# RemoteMain.net
KiCad netlist of a schematic drawn in Altium Designer
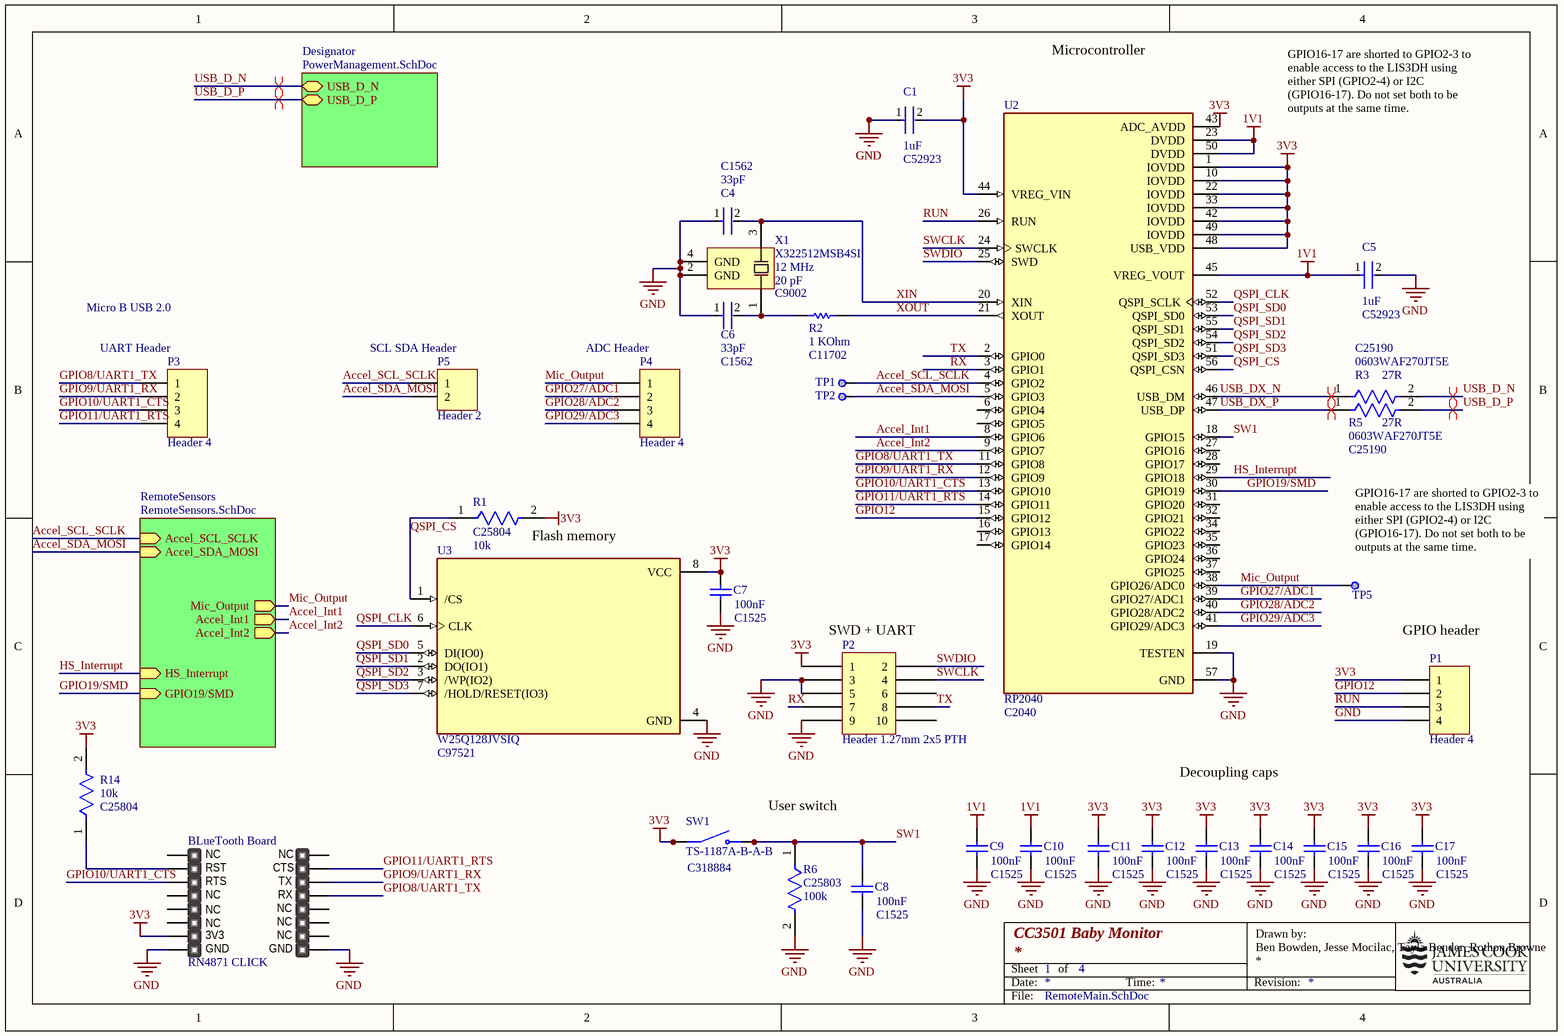
[diagram p0: RemoteMain.SchDoc]

(export (version "E")
  (design (tool "Eeschema 10.0.6"))
  (components
    (comp (ref "BLueTooth Board")
      (value "RN4871 CLICK")
      (footprint "mikroBUS - Large")
      (description "mikroBUS compatible add-on board")
      (libsource (lib "James Cook University") (part "RN4871 Click"))
    )
    (comp (ref "C1")
      (value "CL05A105KA5NQNC")
      (footprint "FP-CL542-IPC_C")
      (description "Cap Ceramic 1uF 25V X5R ±10% SMD 0402 +85°C Paper T/R")
      (fields
        (field (name "JLCPCB PART") "C52923")
        (field (name "CAPACITANCE") "1uF")
        (field (name "TOLERANCE") "10%")
      )
      (libsource (lib "James Cook University") (part "b4654b650e69147ec39a6b967a45e02"))
    )
    (comp (ref "C4")
      (value "0402CG330J500NT")
      (footprint "FP-0402-L_1_0_1-W_0_5_0_1-IPC_A")
      (description "General Purpose Ceramic Capacitor, 0402, 33pF, 5%, C0G, 30ppm/°C, 50V")
      (fields
        (field (name "VOLTAGE") "50V")
        (field (name "JLCPCB PART") "C1562")
        (field (name "CAPACITANCE") "33pF")
        (field (name "TOLERANCE") "5%")
      )
      (libsource (lib "James Cook University") (part "b4654b650e69147ec39a6b967a45e02"))
    )
    (comp (ref "C5")
      (value "CL05A105KA5NQNC")
      (footprint "FP-CL542-IPC_C")
      (description "Cap Ceramic 1uF 25V X5R ±10% SMD 0402 +85°C Paper T/R")
      (fields
        (field (name "JLCPCB PART") "C52923")
        (field (name "CAPACITANCE") "1uF")
        (field (name "TOLERANCE") "10%")
      )
      (libsource (lib "James Cook University") (part "b4654b650e69147ec39a6b967a45e02"))
    )
    (comp (ref "C6")
      (value "0402CG330J500NT")
      (footprint "FP-0402-L_1_0_1-W_0_5_0_1-IPC_A")
      (description "General Purpose Ceramic Capacitor, 0402, 33pF, 5%, C0G, 30ppm/°C, 50V")
      (fields
        (field (name "VOLTAGE") "50V")
        (field (name "JLCPCB PART") "C1562")
        (field (name "CAPACITANCE") "33pF")
        (field (name "TOLERANCE") "5%")
      )
      (libsource (lib "James Cook University") (part "b4654b650e69147ec39a6b967a45e02"))
    )
    (comp (ref "C7")
      (value "CL05B104KO5NNNC")
      (footprint "CAPC1050X55X23ML05T13")
      (description "Chip Capacitor, 100 nF, +/- 10%, 16 V, -55 to 125 degC, 0402 (1005 Metric), RoHS, Tape and Reel")
      (fields
        (field (name "JLCPCB PART") "C1525")
        (field (name "CAPACITANCE") "100nF")
        (field (name "MANUFACTURER") "Samsung Electro-Mechanics")
      )
      (libsource (lib "James Cook University") (part "CAP-NP-2"))
    )
    (comp (ref "C8")
      (value "CL05B104KO5NNNC")
      (footprint "CAPC1050X55X23ML05T13")
      (description "Chip Capacitor, 100 nF, +/- 10%, 16 V, -55 to 125 degC, 0402 (1005 Metric), RoHS, Tape and Reel")
      (fields
        (field (name "JLCPCB PART") "C1525")
        (field (name "CAPACITANCE") "100nF")
        (field (name "MANUFACTURER") "Samsung Electro-Mechanics")
      )
      (libsource (lib "James Cook University") (part "CAP-NP-2"))
    )
    (comp (ref "C9")
      (value "CL05B104KO5NNNC")
      (footprint "CAPC1050X55X23ML05T13")
      (description "Chip Capacitor, 100 nF, +/- 10%, 16 V, -55 to 125 degC, 0402 (1005 Metric), RoHS, Tape and Reel")
      (fields
        (field (name "JLCPCB PART") "C1525")
        (field (name "CAPACITANCE") "100nF")
        (field (name "MANUFACTURER") "Samsung Electro-Mechanics")
      )
      (libsource (lib "James Cook University") (part "CAP-NP-2"))
    )
    (comp (ref "C10")
      (value "CL05B104KO5NNNC")
      (footprint "CAPC1050X55X23ML05T13")
      (description "Chip Capacitor, 100 nF, +/- 10%, 16 V, -55 to 125 degC, 0402 (1005 Metric), RoHS, Tape and Reel")
      (fields
        (field (name "JLCPCB PART") "C1525")
        (field (name "CAPACITANCE") "100nF")
        (field (name "MANUFACTURER") "Samsung Electro-Mechanics")
      )
      (libsource (lib "James Cook University") (part "CAP-NP-2"))
    )
    (comp (ref "C11")
      (value "CL05B104KO5NNNC")
      (footprint "CAPC1050X55X23ML05T13")
      (description "Chip Capacitor, 100 nF, +/- 10%, 16 V, -55 to 125 degC, 0402 (1005 Metric), RoHS, Tape and Reel")
      (fields
        (field (name "JLCPCB PART") "C1525")
        (field (name "CAPACITANCE") "100nF")
        (field (name "MANUFACTURER") "Samsung Electro-Mechanics")
      )
      (libsource (lib "James Cook University") (part "CAP-NP-2"))
    )
    (comp (ref "C12")
      (value "CL05B104KO5NNNC")
      (footprint "CAPC1050X55X23ML05T13")
      (description "Chip Capacitor, 100 nF, +/- 10%, 16 V, -55 to 125 degC, 0402 (1005 Metric), RoHS, Tape and Reel")
      (fields
        (field (name "JLCPCB PART") "C1525")
        (field (name "CAPACITANCE") "100nF")
        (field (name "MANUFACTURER") "Samsung Electro-Mechanics")
      )
      (libsource (lib "James Cook University") (part "CAP-NP-2"))
    )
    (comp (ref "C13")
      (value "CL05B104KO5NNNC")
      (footprint "CAPC1050X55X23ML05T13")
      (description "Chip Capacitor, 100 nF, +/- 10%, 16 V, -55 to 125 degC, 0402 (1005 Metric), RoHS, Tape and Reel")
      (fields
        (field (name "JLCPCB PART") "C1525")
        (field (name "CAPACITANCE") "100nF")
        (field (name "MANUFACTURER") "Samsung Electro-Mechanics")
      )
      (libsource (lib "James Cook University") (part "CAP-NP-2"))
    )
    (comp (ref "C14")
      (value "CL05B104KO5NNNC")
      (footprint "CAPC1050X55X23ML05T13")
      (description "Chip Capacitor, 100 nF, +/- 10%, 16 V, -55 to 125 degC, 0402 (1005 Metric), RoHS, Tape and Reel")
      (fields
        (field (name "JLCPCB PART") "C1525")
        (field (name "CAPACITANCE") "100nF")
        (field (name "MANUFACTURER") "Samsung Electro-Mechanics")
      )
      (libsource (lib "James Cook University") (part "CAP-NP-2"))
    )
    (comp (ref "C15")
      (value "CL05B104KO5NNNC")
      (footprint "CAPC1050X55X23ML05T13")
      (description "Chip Capacitor, 100 nF, +/- 10%, 16 V, -55 to 125 degC, 0402 (1005 Metric), RoHS, Tape and Reel")
      (fields
        (field (name "JLCPCB PART") "C1525")
        (field (name "CAPACITANCE") "100nF")
        (field (name "MANUFACTURER") "Samsung Electro-Mechanics")
      )
      (libsource (lib "James Cook University") (part "CAP-NP-2"))
    )
    (comp (ref "C16")
      (value "CL05B104KO5NNNC")
      (footprint "CAPC1050X55X23ML05T13")
      (description "Chip Capacitor, 100 nF, +/- 10%, 16 V, -55 to 125 degC, 0402 (1005 Metric), RoHS, Tape and Reel")
      (fields
        (field (name "JLCPCB PART") "C1525")
        (field (name "CAPACITANCE") "100nF")
        (field (name "MANUFACTURER") "Samsung Electro-Mechanics")
      )
      (libsource (lib "James Cook University") (part "CAP-NP-2"))
    )
    (comp (ref "C17")
      (value "CL05B104KO5NNNC")
      (footprint "CAPC1050X55X23ML05T13")
      (description "Chip Capacitor, 100 nF, +/- 10%, 16 V, -55 to 125 degC, 0402 (1005 Metric), RoHS, Tape and Reel")
      (fields
        (field (name "JLCPCB PART") "C1525")
        (field (name "CAPACITANCE") "100nF")
        (field (name "MANUFACTURER") "Samsung Electro-Mechanics")
      )
      (libsource (lib "James Cook University") (part "CAP-NP-2"))
    )
    (comp (ref "P1")
      (value "Header 4")
      (footprint "HDR1X4")
      (description "Header, 4-Pin")
      (fields (field (name "PUBLISHER") "Altium Limited"))
      (libsource (lib "James Cook University") (part "Header 4H"))
    )
    (comp (ref "P2")
      (value "Header 1.27mm 2x5 PTH")
      (footprint "Header 1.27mm 2x5 PTH")
      (description "Header 1.27mm pitch, 2x5, PTH through hole")
      (fields (field (name "SOURCE") "JCULibrary.SchLib"))
      (libsource (lib "James Cook University") (part "Header 1.27mm 2x5 PTH"))
    )
    (comp (ref "P3")
      (value "Header 4")
      (footprint "HDR1X4")
      (description "Header, 4-Pin")
      (fields (field (name "PUBLISHER") "Altium Limited"))
      (libsource (lib "James Cook University") (part "Header 4H"))
    )
    (comp (ref "P4")
      (value "Header 4")
      (footprint "HDR1X4")
      (description "Header, 4-Pin")
      (fields (field (name "PUBLISHER") "Altium Limited"))
      (libsource (lib "James Cook University") (part "Header 4H"))
    )
    (comp (ref "P5")
      (value "Header 2")
      (footprint "HDR1X2")
      (description "Header, 2-Pin")
      (fields (field (name "PUBLISHER") "Altium Limited"))
      (libsource (lib "James Cook University") (part "Header 2H"))
    )
    (comp (ref "R1")
      (value "0603WAF1002T5E")
      (footprint "FP-CRCW0603-e3-IPC_B")
      (description "RES Thick Film, 10kΩ, 1%, 0.1W, 100ppm/°C, 0603")
      (fields
        (field (name "TOLERANCE") "1%")
        (field (name "JLCPCB PART") "C25804")
        (field (name "RESISTANCE") "10k")
      )
      (libsource (lib "James Cook University") (part "1029c3af85768c4190bb7ad29bc67b5"))
    )
    (comp (ref "R2")
      (value "0402WGF1001TCE")
      (footprint "RESC1005X40X25NL05T05")
      (description "Chip Resistor, 1 KOhm, +/- 1%, 100 mW, -55 to 155 degC, 0402 (1005 Metric), RoHS, Tape and Reel")
      (fields
        (field (name "RESISTANCE") "1 KOhm")
        (field (name "JLCPCB PART") "C11702")
        (field (name "TOLERANCE") "1%")
        (field (name "MANUFACTURER") "Basic Passives")
      )
      (libsource (lib "James Cook University") (part "RES-2"))
    )
    (comp (ref "R3")
      (value "0603WAF270JT5E")
      (footprint "FP-CRCW0603-e3-IPC_B")
      (description "RES Thick Film, 27Ω, 1%, 0.1W, 200ppm/°C, 0603")
      (fields
        (field (name "JLCPCB PART") "C25190")
        (field (name "RESISTANCE") "27R")
        (field (name "TOLERANCE") "1%")
      )
      (libsource (lib "James Cook University") (part "1029c3af85768c4190bb7ad29bc67b5"))
    )
    (comp (ref "R5")
      (value "0603WAF270JT5E")
      (footprint "FP-CRCW0603-e3-IPC_B")
      (description "RES Thick Film, 27Ω, 1%, 0.1W, 200ppm/°C, 0603")
      (fields
        (field (name "JLCPCB PART") "C25190")
        (field (name "RESISTANCE") "27R")
        (field (name "TOLERANCE") "1%")
      )
      (libsource (lib "James Cook University") (part "1029c3af85768c4190bb7ad29bc67b5"))
    )
    (comp (ref "R6")
      (value "0603WAF1003T5E")
      (footprint "FP-CRCW0603-e3-IPC_B")
      (description "RES Thick Film, 100kΩ, 1%, 0.1W, 100ppm/°C, 0603")
      (fields
        (field (name "JLCPCB PART") "C25803")
        (field (name "RESISTANCE") "100k")
        (field (name "TOLERANCE") "1%")
      )
      (libsource (lib "James Cook University") (part "1029c3af85768c4190bb7ad29bc67b5"))
    )
    (comp (ref "R14")
      (value "0603WAF1002T5E")
      (footprint "FP-CRCW0603-e3-IPC_B")
      (description "RES Thick Film, 10kΩ, 1%, 0.1W, 100ppm/°C, 0603")
      (fields
        (field (name "TOLERANCE") "1%")
        (field (name "JLCPCB PART") "C25804")
        (field (name "RESISTANCE") "10k")
      )
      (libsource (lib "James Cook University") (part "1029c3af85768c4190bb7ad29bc67b5"))
    )
    (comp (ref "SW1")
      (value "TS-1187A-B-A-B")
      (footprint "SW_TS-1187A-B-A-B")
      (description "SPST 50mA @ 12VDC Top Actuated Round Button 160gf SMD Tactile Switches RoHS")
      (fields (field (name "JLCPCB PART") "C318884"))
      (libsource (lib "James Cook University") (part "TS-1187A-B-A-B"))
    )
    (comp (ref "TP1")
      (value "Test point")
      (footprint "Test point-Footprint-1")
      (description "Test point for in-circuit debugging (0.3mm hole, 0.7mm diameter)")
      (libsource (lib "James Cook University") (part "Test point symbol"))
    )
    (comp (ref "TP2")
      (value "Test point")
      (footprint "Test point-Footprint-1")
      (description "Test point for in-circuit debugging (0.3mm hole, 0.7mm diameter)")
      (libsource (lib "James Cook University") (part "Test point symbol"))
    )
    (comp (ref "TP5")
      (value "Test point")
      (footprint "Test point-Footprint-1")
      (description "Test point for in-circuit debugging (0.3mm hole, 0.7mm diameter)")
      (libsource (lib "James Cook University") (part "Test point symbol"))
    )
    (comp (ref "U2")
      (value "RP2040")
      (footprint "QFN40P700X700X90-57N")
      (description "ARM Cortex-M0+ MCU 32-Bit Microcontroller for Raspberry Pi Pico")
      (fields (field (name "JLCPCB PART") "C2040"))
      (libsource (lib "James Cook University") (part "RP2040"))
    )
    (comp (ref "U3")
      (value "W25Q128JVSIQ")
      (footprint "SOIC127P790X216-8N")
      (description "FLASH - NOR Memory IC 128Mb (16M x 8) SPI - Quad I/O, QPI, DTR 133 MHz 8-SOIC")
      (fields (field (name "MF") "Winbond Electronics") (field (name "JLCPCB PART") "C97521"))
      (libsource (lib "James Cook University") (part "W25Q128JVSIQ"))
    )
    (comp (ref "X1")
      (value "X322512MSB4SI")
      (footprint "X322512MSB4SI-Footprint-1")
      (description "12MHz SMD Crystal Resonator 20pF ±10ppm ±30ppm -40℃~+85℃ SMD3225-4P  Crystals ROHS Yangxing Tech")
      (fields
        (field (name "FREQUENCY") "12 MHz")
        (field (name "LOAD CAPACITANCE") "20 pF")
        (field (name "JLCPCB PART") "C9002")
      )
      (libsource (lib "James Cook University") (part "X322512MSB4SI"))
    )
  )
  (nets
    (net (code "1") (name "/Accel_Int1") (class "Default")
      (node (ref "U2") (pin "8") (pinfunction "GPIO6_8") (pintype "bidirectional"))
    )
    (net (code "2") (name "/Accel_Int2") (class "Default")
      (node (ref "U2") (pin "9") (pinfunction "GPIO7_9") (pintype "bidirectional"))
    )
    (net (code "3") (name "/Accel_SCL_SCLK") (class "Default")
      (node (ref "P5") (pin "1") (pinfunction "1_1") (pintype "passive"))
      (node (ref "TP1") (pin "1") (pinfunction "1_1") (pintype "passive"))
      (node (ref "U2") (pin "4") (pinfunction "GPIO2_4") (pintype "bidirectional"))
    )
    (net (code "4") (name "/Accel_SDA_MOSI") (class "Default")
      (node (ref "P5") (pin "2") (pinfunction "2_2") (pintype "passive"))
      (node (ref "TP2") (pin "1") (pinfunction "1_1") (pintype "passive"))
      (node (ref "U2") (pin "5") (pinfunction "GPIO3_5") (pintype "bidirectional"))
    )
    (net (code "5") (name "/GPIO8{slash}UART1_TX") (class "Default")
      (node (ref "BLueTooth Board") (pin "13") (pinfunction "TX_13") (pintype "passive"))
      (node (ref "P3") (pin "1") (pinfunction "1_1") (pintype "passive"))
      (node (ref "U2") (pin "11") (pinfunction "GPIO8_11") (pintype "bidirectional"))
    )
    (net (code "6") (name "/GPIO9{slash}UART1_RX") (class "Default")
      (node (ref "BLueTooth Board") (pin "14") (pinfunction "RX_14") (pintype "passive"))
      (node (ref "P3") (pin "2") (pinfunction "2_2") (pintype "passive"))
      (node (ref "U2") (pin "12") (pinfunction "GPIO9_12") (pintype "bidirectional"))
    )
    (net (code "7") (name "/GPIO10{slash}UART1_CTS") (class "Default")
      (node (ref "BLueTooth Board") (pin "3") (pinfunction "CS_3") (pintype "passive"))
      (node (ref "P3") (pin "3") (pinfunction "3_3") (pintype "passive"))
      (node (ref "U2") (pin "13") (pinfunction "GPIO10_13") (pintype "bidirectional"))
    )
    (net (code "8") (name "/GPIO11{slash}UART1_RTS") (class "Default")
      (node (ref "BLueTooth Board") (pin "15") (pinfunction "INT_15") (pintype "passive"))
      (node (ref "P3") (pin "4") (pinfunction "4_4") (pintype "passive"))
      (node (ref "U2") (pin "14") (pinfunction "GPIO11_14") (pintype "bidirectional"))
    )
    (net (code "9") (name "/GPIO12") (class "Default")
      (node (ref "P1") (pin "2") (pinfunction "2_2") (pintype "passive"))
      (node (ref "U2") (pin "15") (pinfunction "GPIO12_15") (pintype "bidirectional"))
    )
    (net (code "10") (name "/GPIO19{slash}SMD") (class "Default")
      (node (ref "U2") (pin "30") (pinfunction "GPIO19_30") (pintype "bidirectional"))
    )
    (net (code "11") (name "/GPIO27{slash}ADC1") (class "Default")
      (node (ref "P4") (pin "2") (pinfunction "2_2") (pintype "passive"))
      (node (ref "U2") (pin "39") (pinfunction "GPIO27/ADC1_39") (pintype "bidirectional"))
    )
    (net (code "12") (name "/GPIO28{slash}ADC2") (class "Default")
      (node (ref "P4") (pin "3") (pinfunction "3_3") (pintype "passive"))
      (node (ref "U2") (pin "40") (pinfunction "GPIO28/ADC2_40") (pintype "bidirectional"))
    )
    (net (code "13") (name "/GPIO29{slash}ADC3") (class "Default")
      (node (ref "P4") (pin "4") (pinfunction "4_4") (pintype "passive"))
      (node (ref "U2") (pin "41") (pinfunction "GPIO29/ADC3_41") (pintype "bidirectional"))
    )
    (net (code "14") (name "/HS_Interrupt") (class "Default")
      (node (ref "U2") (pin "29") (pinfunction "GPIO18_29") (pintype "bidirectional"))
    )
    (net (code "15") (name "/Mic_Output") (class "Default")
      (node (ref "P4") (pin "1") (pinfunction "1_1") (pintype "passive"))
      (node (ref "TP5") (pin "1") (pinfunction "1_1") (pintype "passive"))
      (node (ref "U2") (pin "38") (pinfunction "GPIO26/ADC0_38") (pintype "bidirectional"))
    )
    (net (code "16") (name "/QSPI_CLK") (class "Default")
      (node (ref "U2") (pin "52") (pinfunction "QSPI_SCLK_52") (pintype "bidirectional"))
      (node (ref "U3") (pin "6") (pinfunction "CLK_6") (pintype "input"))
    )
    (net (code "17") (name "/QSPI_CS") (class "Default")
      (node (ref "R1") (pin "1") (pinfunction "1_1") (pintype "passive"))
      (node (ref "U2") (pin "56") (pinfunction "QSPI_CSN_56") (pintype "bidirectional"))
      (node (ref "U3") (pin "1") (pinfunction "/CS_1") (pintype "input"))
    )
    (net (code "18") (name "/QSPI_SD0") (class "Default")
      (node (ref "U2") (pin "53") (pinfunction "QSPI_SD0_53") (pintype "bidirectional"))
      (node (ref "U3") (pin "5") (pinfunction "DI(IO0)_5") (pintype "bidirectional"))
    )
    (net (code "19") (name "/QSPI_SD1") (class "Default")
      (node (ref "U2") (pin "55") (pinfunction "QSPI_SD1_55") (pintype "bidirectional"))
      (node (ref "U3") (pin "2") (pinfunction "DO(IO1)_2") (pintype "bidirectional"))
    )
    (net (code "20") (name "/QSPI_SD2") (class "Default")
      (node (ref "U2") (pin "54") (pinfunction "QSPI_SD2_54") (pintype "bidirectional"))
      (node (ref "U3") (pin "3") (pinfunction "/WP(IO2)_3") (pintype "bidirectional"))
    )
    (net (code "21") (name "/QSPI_SD3") (class "Default")
      (node (ref "U2") (pin "51") (pinfunction "QSPI_SD3_51") (pintype "bidirectional"))
      (node (ref "U3") (pin "7") (pinfunction "/HOLD/RESET(IO3)_7") (pintype "bidirectional"))
    )
    (net (code "22") (name "/RUN") (class "Default")
      (node (ref "P1") (pin "3") (pinfunction "3_3") (pintype "passive"))
      (node (ref "U2") (pin "26") (pinfunction "RUN_26") (pintype "input"))
    )
    (net (code "23") (name "/RX") (class "Default")
      (node (ref "P2") (pin "7") (pinfunction "7_7") (pintype "passive"))
      (node (ref "U2") (pin "3") (pinfunction "GPIO1_3") (pintype "bidirectional"))
    )
    (net (code "24") (name "/SW1") (class "Default")
      (node (ref "C8") (pin "2") (pinfunction "2_2") (pintype "passive"))
      (node (ref "R6") (pin "1") (pinfunction "1_1") (pintype "passive"))
      (node (ref "SW1") (pin "C") (pinfunction "NO_C") (pintype "passive"))
      (node (ref "SW1") (pin "D") (pinfunction "NO_D") (pintype "passive"))
      (node (ref "U2") (pin "18") (pinfunction "GPIO15_18") (pintype "bidirectional"))
    )
    (net (code "25") (name "/SWCLK") (class "Default")
      (node (ref "P2") (pin "4") (pinfunction "4_4") (pintype "passive"))
      (node (ref "U2") (pin "24") (pinfunction "SWCLK_24") (pintype "input"))
    )
    (net (code "26") (name "/SWDIO") (class "Default")
      (node (ref "P2") (pin "2") (pinfunction "2_2") (pintype "passive"))
      (node (ref "U2") (pin "25") (pinfunction "SWD_25") (pintype "bidirectional"))
    )
    (net (code "27") (name "/TX") (class "Default")
      (node (ref "P2") (pin "8") (pinfunction "8_8") (pintype "passive"))
      (node (ref "U2") (pin "2") (pinfunction "GPIO0_2") (pintype "bidirectional"))
    )
    (net (code "28") (name "/USB_DX_N") (class "Default")
      (node (ref "R3") (pin "1") (pinfunction "1_1") (pintype "passive"))
      (node (ref "U2") (pin "46") (pinfunction "USB_DM_46") (pintype "bidirectional"))
    )
    (net (code "29") (name "/USB_DX_P") (class "Default")
      (node (ref "R5") (pin "1") (pinfunction "1_1") (pintype "passive"))
      (node (ref "U2") (pin "47") (pinfunction "USB_DP_47") (pintype "bidirectional"))
    )
    (net (code "30") (name "/USB_D_N") (class "Default")
      (node (ref "R3") (pin "2") (pinfunction "2_2") (pintype "passive"))
    )
    (net (code "31") (name "/USB_D_P") (class "Default")
      (node (ref "R5") (pin "2") (pinfunction "2_2") (pintype "passive"))
    )
    (net (code "32") (name "/XIN") (class "Default")
      (node (ref "C4") (pin "2") (pinfunction "2_2") (pintype "passive"))
      (node (ref "U2") (pin "20") (pinfunction "XIN_20") (pintype "input"))
      (node (ref "X1") (pin "3") (pinfunction "OSC2_3") (pintype "passive"))
    )
    (net (code "33") (name "/XOUT") (class "Default")
      (node (ref "R2") (pin "2") (pinfunction "2_2") (pintype "passive"))
      (node (ref "U2") (pin "21") (pinfunction "XOUT_21") (pintype "output"))
    )
    (net (code "34") (name "1V1") (class "Default")
      (node (ref "C10") (pin "2") (pinfunction "2_2") (pintype "passive"))
      (node (ref "C5") (pin "1") (pinfunction "1_1") (pintype "passive"))
      (node (ref "C9") (pin "2") (pinfunction "2_2") (pintype "passive"))
      (node (ref "U2") (pin "23") (pinfunction "DVDD_23") (pintype "power_in"))
      (node (ref "U2") (pin "45") (pinfunction "VREG_VOUT_45") (pintype "power_in"))
      (node (ref "U2") (pin "50") (pinfunction "DVDD_50") (pintype "power_in"))
    )
    (net (code "35") (name "3V3") (class "Default")
      (node (ref "BLueTooth Board") (pin "7") (pinfunction "3.3V_7") (pintype "passive"))
      (node (ref "C1") (pin "2") (pinfunction "2_2") (pintype "passive"))
      (node (ref "C11") (pin "2") (pinfunction "2_2") (pintype "passive"))
      (node (ref "C12") (pin "2") (pinfunction "2_2") (pintype "passive"))
      (node (ref "C13") (pin "2") (pinfunction "2_2") (pintype "passive"))
      (node (ref "C14") (pin "2") (pinfunction "2_2") (pintype "passive"))
      (node (ref "C15") (pin "2") (pinfunction "2_2") (pintype "passive"))
      (node (ref "C16") (pin "2") (pinfunction "2_2") (pintype "passive"))
      (node (ref "C17") (pin "2") (pinfunction "2_2") (pintype "passive"))
      (node (ref "C7") (pin "2") (pinfunction "2_2") (pintype "passive"))
      (node (ref "P1") (pin "1") (pinfunction "1_1") (pintype "passive"))
      (node (ref "P2") (pin "1") (pinfunction "1_1") (pintype "passive"))
      (node (ref "R1") (pin "2") (pinfunction "2_2") (pintype "passive"))
      (node (ref "R14") (pin "2") (pinfunction "2_2") (pintype "passive"))
      (node (ref "SW1") (pin "A") (pinfunction "COM_A") (pintype "passive"))
      (node (ref "SW1") (pin "B") (pinfunction "COM_B") (pintype "passive"))
      (node (ref "U2") (pin "1") (pinfunction "IOVDD_1") (pintype "power_in"))
      (node (ref "U2") (pin "10") (pinfunction "IOVDD_10") (pintype "power_in"))
      (node (ref "U2") (pin "22") (pinfunction "IOVDD_22") (pintype "power_in"))
      (node (ref "U2") (pin "33") (pinfunction "IOVDD_33") (pintype "power_in"))
      (node (ref "U2") (pin "42") (pinfunction "IOVDD_42") (pintype "power_in"))
      (node (ref "U2") (pin "43") (pinfunction "ADC_AVDD_43") (pintype "power_in"))
      (node (ref "U2") (pin "44") (pinfunction "VREG_VIN_44") (pintype "input"))
      (node (ref "U2") (pin "48") (pinfunction "USB_VDD_48") (pintype "power_in"))
      (node (ref "U2") (pin "49") (pinfunction "IOVDD_49") (pintype "power_in"))
      (node (ref "U3") (pin "8") (pinfunction "VCC_8") (pintype "power_in"))
    )
    (net (code "36") (name "GND") (class "Default")
      (node (ref "BLueTooth Board") (pin "8") (pinfunction "GND_8") (pintype "passive"))
      (node (ref "BLueTooth Board") (pin "9") (pinfunction "GND_9") (pintype "passive"))
      (node (ref "C1") (pin "1") (pinfunction "1_1") (pintype "passive"))
      (node (ref "C10") (pin "1") (pinfunction "1_1") (pintype "passive"))
      (node (ref "C11") (pin "1") (pinfunction "1_1") (pintype "passive"))
      (node (ref "C12") (pin "1") (pinfunction "1_1") (pintype "passive"))
      (node (ref "C13") (pin "1") (pinfunction "1_1") (pintype "passive"))
      (node (ref "C14") (pin "1") (pinfunction "1_1") (pintype "passive"))
      (node (ref "C15") (pin "1") (pinfunction "1_1") (pintype "passive"))
      (node (ref "C16") (pin "1") (pinfunction "1_1") (pintype "passive"))
      (node (ref "C17") (pin "1") (pinfunction "1_1") (pintype "passive"))
      (node (ref "C4") (pin "1") (pinfunction "1_1") (pintype "passive"))
      (node (ref "C5") (pin "2") (pinfunction "2_2") (pintype "passive"))
      (node (ref "C6") (pin "1") (pinfunction "1_1") (pintype "passive"))
      (node (ref "C7") (pin "1") (pinfunction "1_1") (pintype "passive"))
      (node (ref "C8") (pin "1") (pinfunction "1_1") (pintype "passive"))
      (node (ref "C9") (pin "1") (pinfunction "1_1") (pintype "passive"))
      (node (ref "P1") (pin "4") (pinfunction "4_4") (pintype "passive"))
      (node (ref "P2") (pin "3") (pinfunction "3_3") (pintype "passive"))
      (node (ref "P2") (pin "5") (pinfunction "5_5") (pintype "passive"))
      (node (ref "P2") (pin "9") (pinfunction "9_9") (pintype "passive"))
      (node (ref "R6") (pin "2") (pinfunction "2_2") (pintype "passive"))
      (node (ref "U2") (pin "19") (pinfunction "TESTEN_19") (pintype "passive"))
      (node (ref "U2") (pin "57") (pinfunction "GND_57") (pintype "power_in"))
      (node (ref "U3") (pin "4") (pinfunction "GND_4") (pintype "power_in"))
      (node (ref "X1") (pin "2") (pinfunction "GND_2") (pintype "passive"))
      (node (ref "X1") (pin "4") (pinfunction "GND_4") (pintype "passive"))
    )
    (net (code "37") (name "Net-(BLueTooth Board-RST)") (class "Default")
      (node (ref "BLueTooth Board") (pin "2") (pinfunction "RST_2") (pintype "passive"))
      (node (ref "R14") (pin "1") (pinfunction "1_1") (pintype "passive"))
    )
    (net (code "38") (name "Net-(X1-OSC1)") (class "Default")
      (node (ref "C6") (pin "2") (pinfunction "2_2") (pintype "passive"))
      (node (ref "R2") (pin "1") (pinfunction "1_1") (pintype "passive"))
      (node (ref "X1") (pin "1") (pinfunction "OSC1_1") (pintype "passive"))
    )
    (net (code "39") (name "unconnected-(BLueTooth Board-5V-Pad10)") (class "Default")
      (node (ref "BLueTooth Board") (pin "10") (pinfunction "5V_10") (pintype "passive"))
    )
    (net (code "40") (name "unconnected-(BLueTooth Board-AN-Pad1)") (class "Default")
      (node (ref "BLueTooth Board") (pin "1") (pinfunction "AN_1") (pintype "passive"))
    )
    (net (code "41") (name "unconnected-(BLueTooth Board-MISO-Pad5)") (class "Default")
      (node (ref "BLueTooth Board") (pin "5") (pinfunction "MISO_5") (pintype "passive"))
    )
    (net (code "42") (name "unconnected-(BLueTooth Board-MOSI-Pad6)") (class "Default")
      (node (ref "BLueTooth Board") (pin "6") (pinfunction "MOSI_6") (pintype "passive"))
    )
    (net (code "43") (name "unconnected-(BLueTooth Board-PWM-Pad16)") (class "Default")
      (node (ref "BLueTooth Board") (pin "16") (pinfunction "PWM_16") (pintype "passive"))
    )
    (net (code "44") (name "unconnected-(BLueTooth Board-SCK-Pad4)") (class "Default")
      (node (ref "BLueTooth Board") (pin "4") (pinfunction "SCK_4") (pintype "passive"))
    )
    (net (code "45") (name "unconnected-(BLueTooth Board-SCL-Pad12)") (class "Default")
      (node (ref "BLueTooth Board") (pin "12") (pinfunction "SCL_12") (pintype "passive"))
    )
    (net (code "46") (name "unconnected-(BLueTooth Board-SDA-Pad11)") (class "Default")
      (node (ref "BLueTooth Board") (pin "11") (pinfunction "SDA_11") (pintype "passive"))
    )
    (net (code "47") (name "unconnected-(P2-Pad6)") (class "Default")
      (node (ref "P2") (pin "6") (pinfunction "6_6") (pintype "passive"))
    )
    (net (code "48") (name "unconnected-(P2-Pad10)") (class "Default")
      (node (ref "P2") (pin "10") (pinfunction "10_10") (pintype "passive"))
    )
    (net (code "49") (name "unconnected-(U2-GPIO4-Pad6)") (class "Default")
      (node (ref "U2") (pin "6") (pinfunction "GPIO4_6") (pintype "bidirectional"))
    )
    (net (code "50") (name "unconnected-(U2-GPIO5-Pad7)") (class "Default")
      (node (ref "U2") (pin "7") (pinfunction "GPIO5_7") (pintype "bidirectional"))
    )
    (net (code "51") (name "unconnected-(U2-GPIO13-Pad16)") (class "Default")
      (node (ref "U2") (pin "16") (pinfunction "GPIO13_16") (pintype "bidirectional"))
    )
    (net (code "52") (name "unconnected-(U2-GPIO14-Pad17)") (class "Default")
      (node (ref "U2") (pin "17") (pinfunction "GPIO14_17") (pintype "bidirectional"))
    )
    (net (code "53") (name "unconnected-(U2-GPIO16-Pad27)") (class "Default")
      (node (ref "U2") (pin "27") (pinfunction "GPIO16_27") (pintype "bidirectional"))
    )
    (net (code "54") (name "unconnected-(U2-GPIO17-Pad28)") (class "Default")
      (node (ref "U2") (pin "28") (pinfunction "GPIO17_28") (pintype "bidirectional"))
    )
    (net (code "55") (name "unconnected-(U2-GPIO20-Pad31)") (class "Default")
      (node (ref "U2") (pin "31") (pinfunction "GPIO20_31") (pintype "bidirectional"))
    )
    (net (code "56") (name "unconnected-(U2-GPIO21-Pad32)") (class "Default")
      (node (ref "U2") (pin "32") (pinfunction "GPIO21_32") (pintype "bidirectional"))
    )
    (net (code "57") (name "unconnected-(U2-GPIO22-Pad34)") (class "Default")
      (node (ref "U2") (pin "34") (pinfunction "GPIO22_34") (pintype "bidirectional"))
    )
    (net (code "58") (name "unconnected-(U2-GPIO23-Pad35)") (class "Default")
      (node (ref "U2") (pin "35") (pinfunction "GPIO23_35") (pintype "bidirectional"))
    )
    (net (code "59") (name "unconnected-(U2-GPIO24-Pad36)") (class "Default")
      (node (ref "U2") (pin "36") (pinfunction "GPIO24_36") (pintype "bidirectional"))
    )
    (net (code "60") (name "unconnected-(U2-GPIO25-Pad37)") (class "Default")
      (node (ref "U2") (pin "37") (pinfunction "GPIO25_37") (pintype "bidirectional"))
    )
  )
)
